# Adafruit_Gemma_rev_B.net
KiCad netlist of a schematic drawn in EAGLE
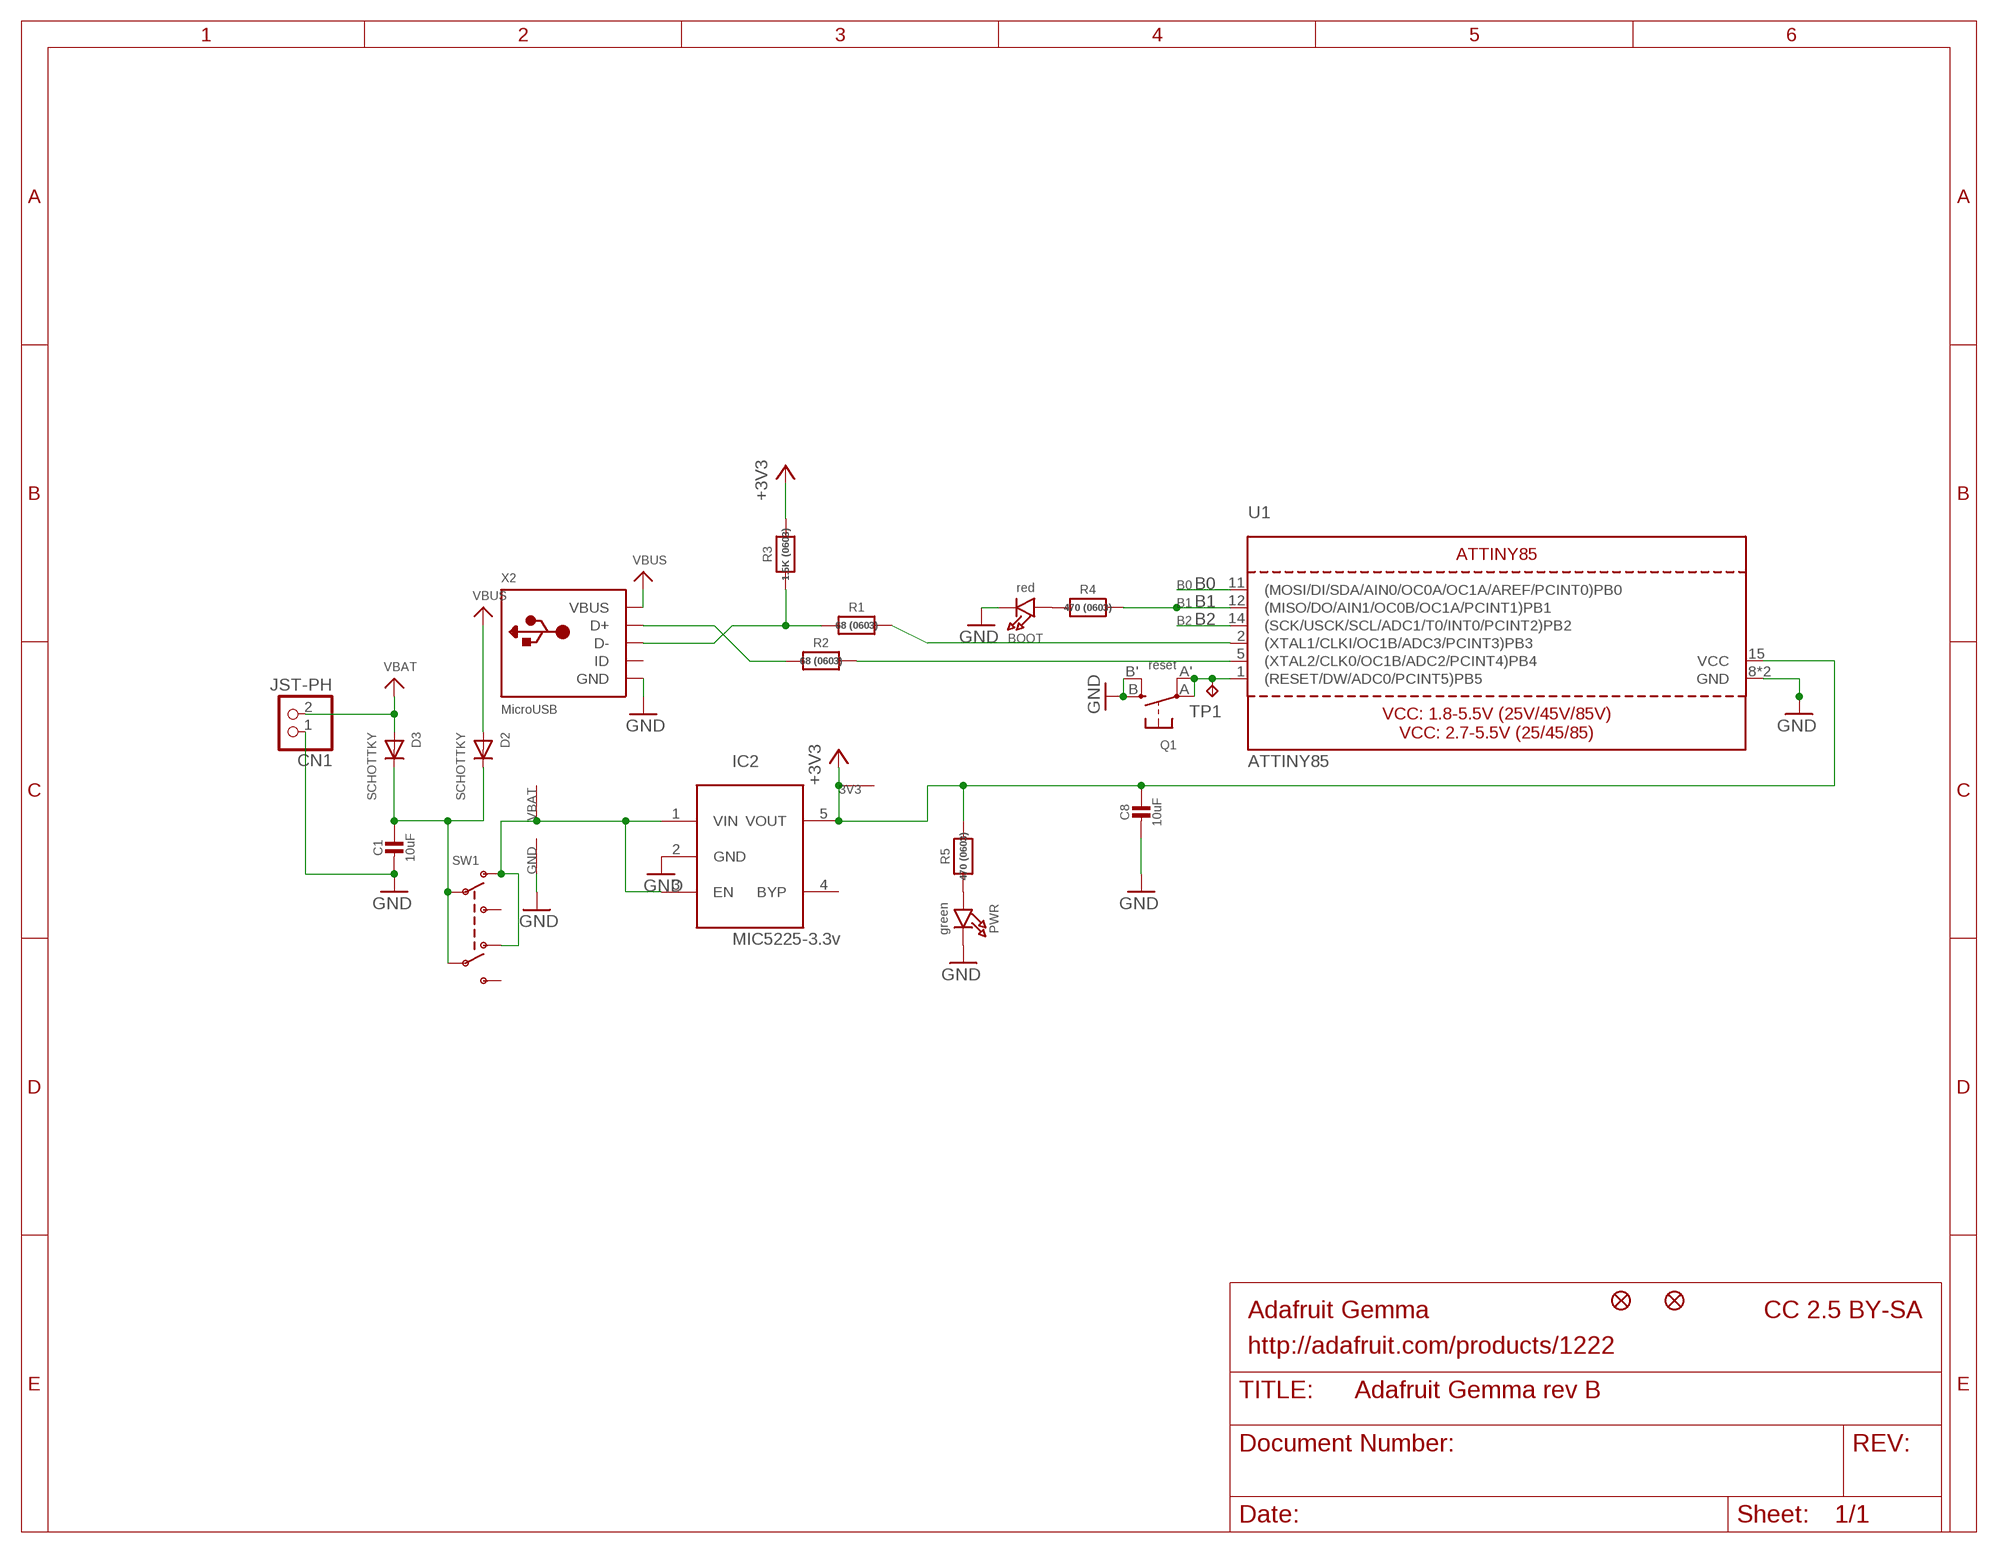
[diagram p0: schematic, sheet 1]

(export (version "E")
  (design (tool "Eeschema 10.0.6"))
  (components
    (comp (ref "3V3")
      (value "SEWTAP-2.0IN")
      (footprint "eagle-import:SEWINGTAP_2.0")
      (libsource (lib "eagle-import") (part "SEWTAP-2.0IN"))
    )
    (comp (ref "B0")
      (value "SEWTAP-2.0IN")
      (footprint "eagle-import:SEWINGTAP_2.0")
      (libsource (lib "eagle-import") (part "SEWTAP-2.0IN"))
    )
    (comp (ref "B1")
      (value "SEWTAP-2.0IN")
      (footprint "eagle-import:SEWINGTAP_2.0")
      (libsource (lib "eagle-import") (part "SEWTAP-2.0IN"))
    )
    (comp (ref "B2")
      (value "SEWTAP-2.0IN")
      (footprint "eagle-import:SEWINGTAP_2.0")
      (libsource (lib "eagle-import") (part "SEWTAP-2.0IN"))
    )
    (comp (ref "BOOT")
      (value "red")
      (footprint "eagle-import:CHIPLED_0805_NOOUTLINE")
      (libsource (lib "eagle-import") (part "LED0805_NOOUTLINE"))
    )
    (comp (ref "C1")
      (value "10uF")
      (footprint "eagle-import:0805-NO")
      (libsource (lib "eagle-import") (part "CAP_CERAMIC0805-NOOUTLINE"))
    )
    (comp (ref "C8")
      (value "10uF")
      (footprint "eagle-import:0805-NO")
      (libsource (lib "eagle-import") (part "CAP_CERAMIC0805-NOOUTLINE"))
    )
    (comp (ref "CN1")
      (value "JST-PH")
      (footprint "eagle-import:JSTPH2")
      (libsource (lib "eagle-import") (part "CON_JST_PH_2PIN"))
    )
    (comp (ref "D2")
      (value "SCHOTTKY")
      (footprint "eagle-import:SOD-123FL")
      (libsource (lib "eagle-import") (part "DIODE_SOD-123FL"))
    )
    (comp (ref "D3")
      (value "SCHOTTKY")
      (footprint "eagle-import:SOD-123FL")
      (libsource (lib "eagle-import") (part "DIODE_SOD-123FL"))
    )
    (comp (ref "GND")
      (value "SEWTAP-2.0IN")
      (footprint "eagle-import:SEWINGTAP_2.0")
      (libsource (lib "eagle-import") (part "SEWTAP-2.0IN"))
    )
    (comp (ref "IC2")
      (value "MIC5225-3.3v")
      (footprint "eagle-import:SOT23-5L")
      (libsource (lib "eagle-import") (part "LP298XS"))
    )
    (comp (ref "PWR")
      (value "green")
      (footprint "eagle-import:CHIPLED_0805_NOOUTLINE")
      (libsource (lib "eagle-import") (part "LED0805_NOOUTLINE"))
    )
    (comp (ref "Q1")
      (value "reset")
      (footprint "eagle-import:BTN_KMR2_4.6X2.8")
      (libsource (lib "eagle-import") (part "SWITCH_TACT_SMT4.6X2.8"))
    )
    (comp (ref "R1")
      (value "68 (0603)")
      (footprint "eagle-import:0603-NO")
      (libsource (lib "eagle-import") (part "RESISTOR_0603_NOOUT"))
    )
    (comp (ref "R2")
      (value "68 (0603)")
      (footprint "eagle-import:0603-NO")
      (libsource (lib "eagle-import") (part "RESISTOR_0603_NOOUT"))
    )
    (comp (ref "R3")
      (value "1.5K (0603)")
      (footprint "eagle-import:0603-NO")
      (libsource (lib "eagle-import") (part "RESISTOR_0603_NOOUT"))
    )
    (comp (ref "R4")
      (value "470 (0603)")
      (footprint "eagle-import:0603-NO")
      (libsource (lib "eagle-import") (part "RESISTOR_0603_NOOUT"))
    )
    (comp (ref "R5")
      (value "470 (0603)")
      (footprint "eagle-import:0603-NO")
      (libsource (lib "eagle-import") (part "RESISTOR_0603_NOOUT"))
    )
    (comp (ref "SW1")
      (value "SWITCH_DPDTEG1390")
      (footprint "eagle-import:EG1390")
      (libsource (lib "eagle-import") (part "SWITCH_DPDTEG1390"))
    )
    (comp (ref "TP1")
      (value "TPB2,54")
      (footprint "eagle-import:B2,54")
      (libsource (lib "eagle-import") (part "TPB2,54"))
    )
    (comp (ref "U$1")
      (value "FIDUCIAL\"\"")
      (footprint "eagle-import:FIDUCIAL_1MM")
      (libsource (lib "eagle-import") (part "FIDUCIAL{dblquote}{dblquote}"))
    )
    (comp (ref "U$6")
      (value "FIDUCIAL\"\"")
      (footprint "eagle-import:FIDUCIAL_1MM")
      (libsource (lib "eagle-import") (part "FIDUCIAL{dblquote}{dblquote}"))
    )
    (comp (ref "U1")
      (value "ATTINY85")
      (footprint "eagle-import:MLF20_4X4MM_0.5MM_ATMEL")
      (libsource (lib "eagle-import") (part "ATTINY85"))
    )
    (comp (ref "VBAT")
      (value "SEWTAP-2.0IN")
      (footprint "eagle-import:SEWINGTAP_2.0")
      (libsource (lib "eagle-import") (part "SEWTAP-2.0IN"))
    )
    (comp (ref "X2")
      (value "MicroUSB")
      (footprint "eagle-import:4UCONN_20329")
      (libsource (lib "eagle-import") (part "USBMICRO_20329"))
    )
  )
  (nets
    (net (code "1") (name "+3V3") (class "Default")
      (node (ref "3V3") (pin "P$1") (pinfunction "SEW_P$1") (pintype "bidirectional"))
      (node (ref "C8") (pin "1") (pinfunction "1_1") (pintype "passive"))
      (node (ref "IC2") (pin "5") (pinfunction "VOUT_5") (pintype "bidirectional"))
      (node (ref "R3") (pin "2") (pinfunction "2_2") (pintype "passive"))
      (node (ref "R5") (pin "2") (pinfunction "2_2") (pintype "passive"))
      (node (ref "U1") (pin "15") (pinfunction "VCC_15") (pintype "power_in"))
    )
    (net (code "2") (name "/B0") (class "Default")
      (node (ref "B0") (pin "P$1") (pinfunction "SEW_P$1") (pintype "bidirectional"))
      (node (ref "U1") (pin "11") (pinfunction "(MOSI/DI/SDA/AIN0/OC0A/OC1A/AREF/PCINT0)PB0_11") (pintype "bidirectional"))
    )
    (net (code "3") (name "/B1") (class "Default")
      (node (ref "B1") (pin "P$1") (pinfunction "SEW_P$1") (pintype "bidirectional"))
      (node (ref "R4") (pin "2") (pinfunction "2_2") (pintype "passive"))
      (node (ref "U1") (pin "12") (pinfunction "(MISO/DO/AIN1/OC0B/OC1A/PCINT1)PB1_12") (pintype "bidirectional"))
    )
    (net (code "4") (name "/B2") (class "Default")
      (node (ref "B2") (pin "P$1") (pinfunction "SEW_P$1") (pintype "bidirectional"))
      (node (ref "U1") (pin "14") (pinfunction "(SCK/USCK/SCL/ADC1/T0/INT0/PCINT2)PB2_14") (pintype "bidirectional"))
    )
    (net (code "5") (name "GND") (class "Default")
      (node (ref "BOOT") (pin "C") (pinfunction "C_C") (pintype "passive"))
      (node (ref "C1") (pin "2") (pinfunction "2_2") (pintype "passive"))
      (node (ref "C8") (pin "2") (pinfunction "2_2") (pintype "passive"))
      (node (ref "CN1") (pin "1") (pinfunction "1_1") (pintype "passive"))
      (node (ref "GND") (pin "P$1") (pinfunction "SEW_P$1") (pintype "bidirectional"))
      (node (ref "IC2") (pin "2") (pinfunction "GND_2") (pintype "bidirectional"))
      (node (ref "PWR") (pin "C") (pinfunction "C_C") (pintype "passive"))
      (node (ref "Q1") (pin "B") (pinfunction "S_B") (pintype "passive"))
      (node (ref "Q1") (pin "B'") (pinfunction "S1_B'") (pintype "passive"))
      (node (ref "U1") (pin "8") (pinfunction "GND_8") (pintype "power_in"))
      (node (ref "U1") (pin "THERMAL") (pinfunction "GND_THERMAL") (pintype "power_in"))
      (node (ref "X2") (pin "BASE@1") (pinfunction "GND_BASE@1") (pintype "power_in"))
      (node (ref "X2") (pin "BASE@2") (pinfunction "GND_BASE@2") (pintype "power_in"))
      (node (ref "X2") (pin "GND") (pinfunction "GND_GND") (pintype "power_in"))
      (node (ref "X2") (pin "SPRT@1") (pinfunction "GND_SPRT@1") (pintype "power_in"))
      (node (ref "X2") (pin "SPRT@2") (pinfunction "GND_SPRT@2") (pintype "power_in"))
      (node (ref "X2") (pin "SPRT@3") (pinfunction "GND_SPRT@3") (pintype "power_in"))
      (node (ref "X2") (pin "SPRT@4") (pinfunction "GND_SPRT@4") (pintype "power_in"))
    )
    (net (code "6") (name "Net-(BOOT-PadA)") (class "Default")
      (node (ref "BOOT") (pin "A") (pinfunction "A_A") (pintype "passive"))
      (node (ref "R4") (pin "1") (pinfunction "1_1") (pintype "passive"))
    )
    (net (code "7") (name "Net-(C1-Pad1)") (class "Default")
      (node (ref "C1") (pin "1") (pinfunction "1_1") (pintype "passive"))
      (node (ref "D2") (pin "C") (pinfunction "C_C") (pintype "passive"))
      (node (ref "D3") (pin "C") (pinfunction "C_C") (pintype "passive"))
      (node (ref "SW1") (pin "P1") (pinfunction "P1_P1") (pintype "passive"))
      (node (ref "SW1") (pin "P2") (pinfunction "P2_P2") (pintype "passive"))
    )
    (net (code "8") (name "Net-(IC2-EN)") (class "Default")
      (node (ref "IC2") (pin "1") (pinfunction "VIN_1") (pintype "bidirectional"))
      (node (ref "IC2") (pin "3") (pinfunction "EN_3") (pintype "bidirectional"))
      (node (ref "SW1") (pin "O1") (pinfunction "O1_O1") (pintype "passive"))
      (node (ref "SW1") (pin "O2") (pinfunction "O2_O2") (pintype "passive"))
      (node (ref "VBAT") (pin "P$1") (pinfunction "SEW_P$1") (pintype "bidirectional"))
    )
    (net (code "9") (name "Net-(PWR-PadA)") (class "Default")
      (node (ref "PWR") (pin "A") (pinfunction "A_A") (pintype "passive"))
      (node (ref "R5") (pin "1") (pinfunction "1_1") (pintype "passive"))
    )
    (net (code "10") (name "Net-(Q1-P)") (class "Default")
      (node (ref "Q1") (pin "A") (pinfunction "P_A") (pintype "passive"))
      (node (ref "Q1") (pin "A'") (pinfunction "P1_A'") (pintype "passive"))
      (node (ref "TP1") (pin "TP") (pinfunction "TP_TP") (pintype "input"))
      (node (ref "U1") (pin "1") (pinfunction "(RESET/DW/ADC0/PCINT5)PB5_1") (pintype "bidirectional"))
    )
    (net (code "11") (name "Net-(R1-Pad1)") (class "Default")
      (node (ref "R1") (pin "1") (pinfunction "1_1") (pintype "passive"))
      (node (ref "R3") (pin "1") (pinfunction "1_1") (pintype "passive"))
      (node (ref "X2") (pin "D-") (pinfunction "D-_D-") (pintype "bidirectional"))
    )
    (net (code "12") (name "Net-(R2-Pad1)") (class "Default")
      (node (ref "R2") (pin "1") (pinfunction "1_1") (pintype "passive"))
      (node (ref "X2") (pin "D+") (pinfunction "D+_D+") (pintype "bidirectional"))
    )
    (net (code "13") (name "Net-(U1-(XTAL1{slash}CLKI{slash}OC1B{slash}ADC3{slash}PCINT3)PB3)") (class "Default")
      (node (ref "R1") (pin "2") (pinfunction "2_2") (pintype "passive"))
      (node (ref "U1") (pin "2") (pinfunction "(XTAL1/CLKI/OC1B/ADC3/PCINT3)PB3_2") (pintype "bidirectional"))
    )
    (net (code "14") (name "Net-(U1-(XTAL2{slash}CLK0{slash}OC1B{slash}ADC2{slash}PCINT4)PB4)") (class "Default")
      (node (ref "R2") (pin "2") (pinfunction "2_2") (pintype "passive"))
      (node (ref "U1") (pin "5") (pinfunction "(XTAL2/CLK0/OC1B/ADC2/PCINT4)PB4_5") (pintype "bidirectional"))
    )
    (net (code "15") (name "VBAT") (class "Default")
      (node (ref "CN1") (pin "2") (pinfunction "2_2") (pintype "passive"))
      (node (ref "D3") (pin "A") (pinfunction "A_A") (pintype "passive"))
    )
    (net (code "16") (name "VBUS") (class "Default")
      (node (ref "D2") (pin "A") (pinfunction "A_A") (pintype "passive"))
      (node (ref "X2") (pin "VBUS") (pinfunction "VBUS_VBUS") (pintype "power_in"))
    )
    (net (code "17") (name "unconnected-(IC2-BYP-Pad4)") (class "Default")
      (node (ref "IC2") (pin "4") (pinfunction "BYP_4") (pintype "bidirectional"))
    )
    (net (code "18") (name "unconnected-(SW1-PadS1)") (class "Default")
      (node (ref "SW1") (pin "S1") (pinfunction "S1_S1") (pintype "passive"))
    )
    (net (code "19") (name "unconnected-(SW1-PadS2)") (class "Default")
      (node (ref "SW1") (pin "S2") (pinfunction "S2_S2") (pintype "passive"))
    )
    (net (code "20") (name "unconnected-(X2-PadID)") (class "Default")
      (node (ref "X2") (pin "ID") (pinfunction "ID_ID") (pintype "bidirectional"))
    )
  )
)
